# khoa_so_dien_tu.net
KiCad netlist of a schematic drawn in Altium Designer
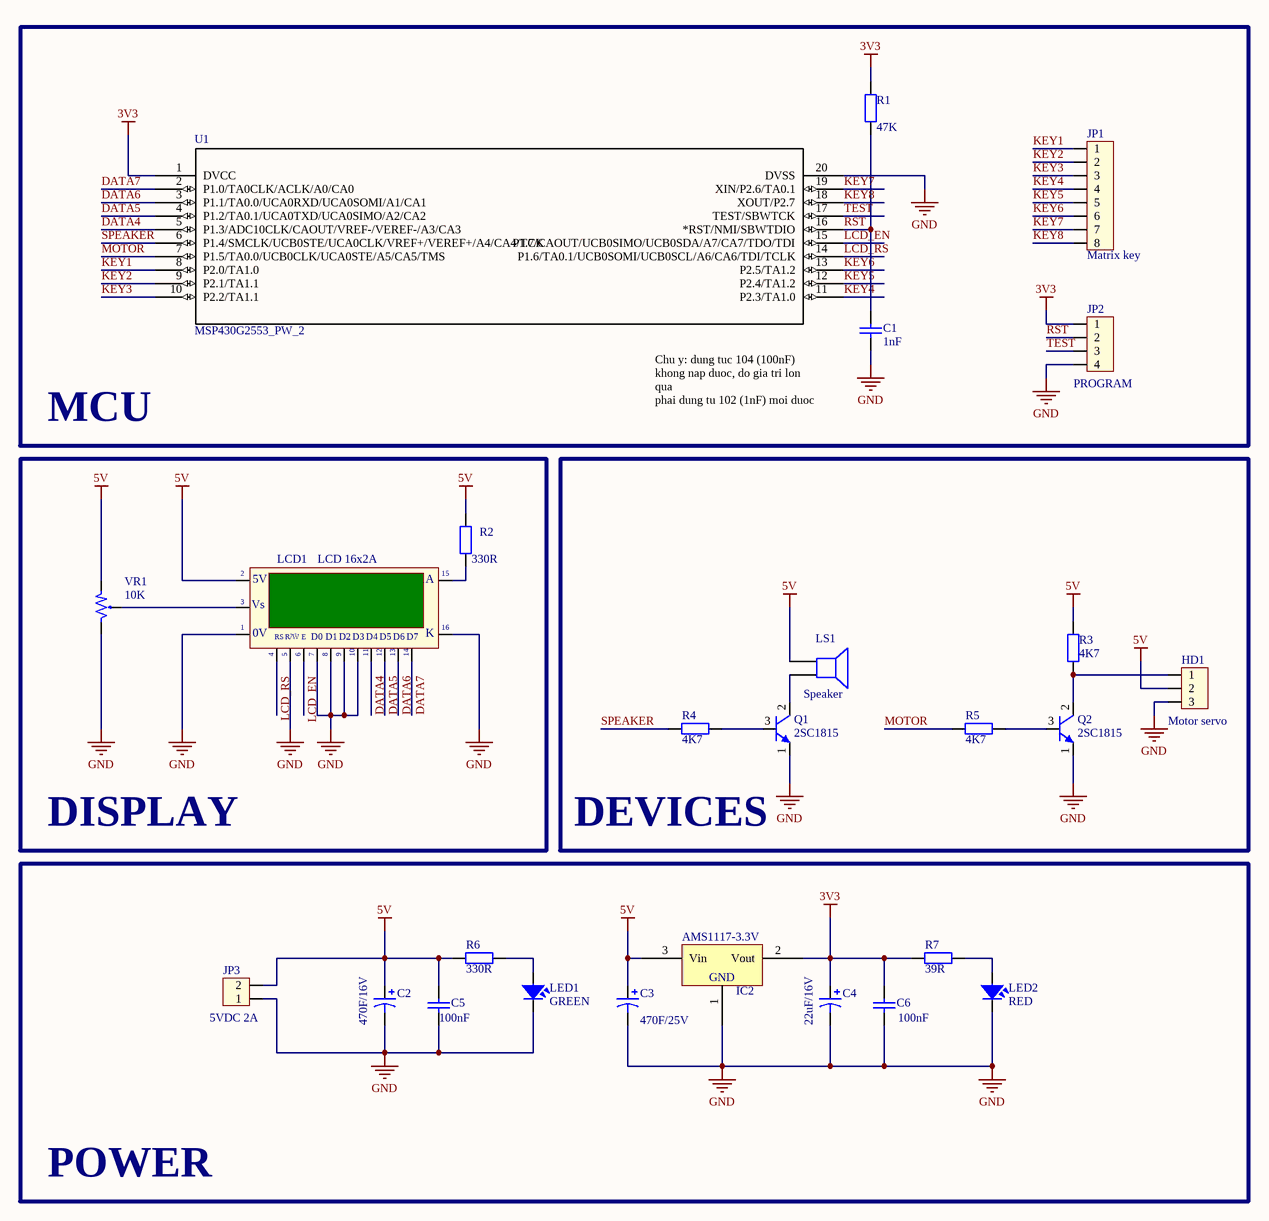
[diagram p0: khoa so dien tu.SchDoc]

(export (version "E")
  (design (tool "Eeschema 10.0.6"))
  (components
    (comp (ref "C1")
      (value "1nF")
      (footprint "Tu gom 104")
      (description "Capacitor")
      (fields (field (name "Comment") "Cap") (field (name "PUBLISHER") "Altium Limited"))
      (libsource (lib "Miscellaneous Devices") (part "Cap"))
    )
    (comp (ref "C2")
      (value "470F/16V")
      (footprint "CAP_470UF_16V")
      (description "Polarized Capacitor (Radial)")
      (fields (field (name "Comment") "Cap Pol1") (field (name "PUBLISHER") "Altium Limited"))
      (libsource (lib "Miscellaneous Devices") (part "Cap Pol1"))
    )
    (comp (ref "C3")
      (value "470F/25V")
      (footprint "CAP_470UF_25V")
      (description "Polarized Capacitor (Radial)")
      (fields (field (name "Comment") "Cap Pol1") (field (name "PUBLISHER") "Altium Limited"))
      (libsource (lib "Miscellaneous Devices") (part "Cap Pol1"))
    )
    (comp (ref "C4")
      (value "22uF/16V")
      (footprint "CAP_22UF_16V")
      (description "Polarized Capacitor (Radial)")
      (fields (field (name "Comment") "Cap Pol1") (field (name "PUBLISHER") "Altium Limited"))
      (libsource (lib "Miscellaneous Devices") (part "Cap Pol1"))
    )
    (comp (ref "C5")
      (value "100nF")
      (footprint "Tu gom 104")
      (description "Capacitor")
      (fields (field (name "Comment") "Cap") (field (name "PUBLISHER") "Altium Limited"))
      (libsource (lib "Miscellaneous Devices") (part "Cap"))
    )
    (comp (ref "C6")
      (value "100nF")
      (footprint "Tu gom 104")
      (description "Capacitor")
      (fields (field (name "Comment") "Cap") (field (name "PUBLISHER") "Altium Limited"))
      (libsource (lib "Miscellaneous Devices") (part "Cap"))
    )
    (comp (ref "HD1")
      (value "Motor servo")
      (footprint "Header_3")
      (description "Header 3 (Green)")
      (libsource (lib "lpson") (part "Hed3"))
    )
    (comp (ref "IC2")
      (value "AMS1117-3.3V")
      (footprint "AMS1117-3.3V")
      (libsource (lib "LuanVanPIR") (part "AMS1117"))
    )
    (comp (ref "JP1")
      (value "Matrix key")
      (footprint "Header_8")
      (description "Connector 8")
      (libsource (lib "lpson") (part "Con8"))
    )
    (comp (ref "JP2")
      (value "PROGRAM")
      (footprint "Header_4")
      (description "Connector 4")
      (libsource (lib "lpson") (part "Con4"))
    )
    (comp (ref "JP3")
      (value "5VDC 2A")
      (footprint "CON2")
      (description "Connector 2")
      (libsource (lib "lpson") (part "Con2"))
    )
    (comp (ref "LCD1")
      (value "LCD 16x2A")
      (footprint "LCD16x2")
      (description "LCD dipslay 16 char, 2 line")
      (libsource (lib "VNELEK") (part "LCD16x2A"))
    )
    (comp (ref "LED1")
      (value "GREEN")
      (footprint "LED3G")
      (description "LED Single colour Green and Red")
      (libsource (lib "VNELEK") (part "LED"))
    )
    (comp (ref "LED2")
      (value "RED")
      (footprint "LED3R")
      (description "LED Single colour Green and Red")
      (libsource (lib "VNELEK") (part "LED"))
    )
    (comp (ref "LS1")
      (value "Speaker")
      (footprint "SPEAKER")
      (description "Loudspeaker")
      (fields (field (name "PUBLISHER") "Altium Limited"))
      (libsource (lib "Miscellaneous Devices") (part "Speaker"))
    )
    (comp (ref "Q1")
      (value "2SC1815")
      (footprint "2SC1815")
      (description "Trans NPN 50V 150mA TO-92")
      (libsource (lib "lpson") (part "2SC1815"))
    )
    (comp (ref "Q2")
      (value "2SC1815")
      (footprint "2SC1815")
      (description "Trans NPN 50V 150mA TO-92")
      (libsource (lib "lpson") (part "2SC1815"))
    )
    (comp (ref "R1")
      (value "47K")
      (footprint "RES 1/4W CFR25")
      (description "Resistor")
      (fields (field (name "Comment") "Res2") (field (name "PUBLISHER") "Altium Limited"))
      (libsource (lib "") (part "Res2_2"))
    )
    (comp (ref "R2")
      (value "330R")
      (footprint "RES 1/4W CFR25")
      (description "Resistor")
      (fields (field (name "Comment") "Res2") (field (name "PUBLISHER") "Altium Limited"))
      (libsource (lib "") (part "Res2_2"))
    )
    (comp (ref "R3")
      (value "4K7")
      (footprint "RES 1/4W CFR25")
      (description "Resistor")
      (fields (field (name "Comment") "Res2") (field (name "PUBLISHER") "Altium Limited"))
      (libsource (lib "") (part "Res2_2"))
    )
    (comp (ref "R4")
      (value "4K7")
      (footprint "RES 1/4W CFR25")
      (description "Resistor")
      (fields (field (name "Comment") "Res2") (field (name "PUBLISHER") "Altium Limited"))
      (libsource (lib "Miscellaneous Devices") (part "Res2"))
    )
    (comp (ref "R5")
      (value "4K7")
      (footprint "RES 1/4W CFR25")
      (description "Resistor")
      (fields (field (name "Comment") "Res2") (field (name "PUBLISHER") "Altium Limited"))
      (libsource (lib "Miscellaneous Devices") (part "Res2"))
    )
    (comp (ref "R6")
      (value "330R")
      (footprint "RES 1/4W CFR25")
      (description "Resistor")
      (fields (field (name "Comment") "Res2") (field (name "PUBLISHER") "Altium Limited"))
      (libsource (lib "") (part "Res2_1"))
    )
    (comp (ref "R7")
      (value "39R")
      (footprint "RES 1/4W CFR25")
      (description "Resistor")
      (fields (field (name "Comment") "Res2") (field (name "PUBLISHER") "Altium Limited"))
      (libsource (lib "") (part "Res2_1"))
    )
    (comp (ref "U1")
      (value "MSP430G2553_PW_2")
      (footprint "MSP430G2553")
      (description "Imported")
      (fields
        (field (name "MANUFACTURER_PART_NUMBER") "msp430g2553_pw_20")
        (field (name "GENERIC_PART_NUMBER") "MSP430G2553")
      )
      (libsource (lib "MSP430G2553_PW_2") (part "MSP430G2553_PW_2"))
    )
    (comp (ref "VR1")
      (value "10K")
      (footprint "VR1")
      (description "Var Resistor")
      (libsource (lib "VNELEK") (part "VR1"))
    )
  )
  (nets
    (net (code "1") (name "/DATA4") (class "Default")
      (node (ref "LCD1") (pin "11") (pinfunction "D4_11") (pintype "passive"))
      (node (ref "U1") (pin "5") (pinfunction "P1.3/ADC10CLK/CAOUT/VREF-/VEREF-/A3/CA3_5") (pintype "bidirectional"))
    )
    (net (code "2") (name "/DATA5") (class "Default")
      (node (ref "LCD1") (pin "12") (pinfunction "D5_12") (pintype "passive"))
      (node (ref "U1") (pin "4") (pinfunction "P1.2/TA0.1/UCA0TXD/UCA0SIMO/A2/CA2_4") (pintype "bidirectional"))
    )
    (net (code "3") (name "/DATA6") (class "Default")
      (node (ref "LCD1") (pin "13") (pinfunction "D6_13") (pintype "passive"))
      (node (ref "U1") (pin "3") (pinfunction "P1.1/TA0.0/UCA0RXD/UCA0SOMI/A1/CA1_3") (pintype "bidirectional"))
    )
    (net (code "4") (name "/DATA7") (class "Default")
      (node (ref "LCD1") (pin "14") (pinfunction "D7_14") (pintype "passive"))
      (node (ref "U1") (pin "2") (pinfunction "P1.0/TA0CLK/ACLK/A0/CA0_2") (pintype "bidirectional"))
    )
    (net (code "5") (name "/KEY1") (class "Default")
      (node (ref "JP1") (pin "1") (pinfunction "1_1") (pintype "passive"))
      (node (ref "U1") (pin "8") (pinfunction "P2.0/TA1.0_8") (pintype "bidirectional"))
    )
    (net (code "6") (name "/KEY2") (class "Default")
      (node (ref "JP1") (pin "2") (pinfunction "2_2") (pintype "passive"))
      (node (ref "U1") (pin "9") (pinfunction "P2.1/TA1.1_9") (pintype "bidirectional"))
    )
    (net (code "7") (name "/KEY3") (class "Default")
      (node (ref "JP1") (pin "3") (pinfunction "3_3") (pintype "passive"))
      (node (ref "U1") (pin "10") (pinfunction "P2.2/TA1.1_10") (pintype "bidirectional"))
    )
    (net (code "8") (name "/KEY4") (class "Default")
      (node (ref "JP1") (pin "4") (pinfunction "4_4") (pintype "passive"))
      (node (ref "U1") (pin "11") (pinfunction "P2.3/TA1.0_11") (pintype "bidirectional"))
    )
    (net (code "9") (name "/KEY5") (class "Default")
      (node (ref "JP1") (pin "5") (pinfunction "5_5") (pintype "passive"))
      (node (ref "U1") (pin "12") (pinfunction "P2.4/TA1.2_12") (pintype "bidirectional"))
    )
    (net (code "10") (name "/KEY6") (class "Default")
      (node (ref "JP1") (pin "6") (pinfunction "6_6") (pintype "passive"))
      (node (ref "U1") (pin "13") (pinfunction "P2.5/TA1.2_13") (pintype "bidirectional"))
    )
    (net (code "11") (name "/KEY7") (class "Default")
      (node (ref "JP1") (pin "7") (pinfunction "7_7") (pintype "passive"))
      (node (ref "U1") (pin "19") (pinfunction "XIN/P2.6/TA0.1_19") (pintype "bidirectional"))
    )
    (net (code "12") (name "/KEY8") (class "Default")
      (node (ref "JP1") (pin "8") (pinfunction "8_8") (pintype "passive"))
      (node (ref "U1") (pin "18") (pinfunction "XOUT/P2.7_18") (pintype "bidirectional"))
    )
    (net (code "13") (name "/LCD_EN") (class "Default")
      (node (ref "LCD1") (pin "6") (pinfunction "~{EN}_6") (pintype "passive"))
      (node (ref "U1") (pin "15") (pinfunction "P1.7/CAOUT/UCB0SIMO/UCB0SDA/A7/CA7/TDO/TDI_15") (pintype "bidirectional"))
    )
    (net (code "14") (name "/LCD_RS") (class "Default")
      (node (ref "LCD1") (pin "4") (pinfunction "RS_4") (pintype "passive"))
      (node (ref "U1") (pin "14") (pinfunction "P1.6/TA0.1/UCB0SOMI/UCB0SCL/A6/CA6/TDI/TCLK_14") (pintype "bidirectional"))
    )
    (net (code "15") (name "/MOTOR") (class "Default")
      (node (ref "R5") (pin "1") (pinfunction "1_1") (pintype "passive"))
      (node (ref "U1") (pin "7") (pinfunction "P1.5/TA0.0/UCB0CLK/UCA0STE/A5/CA5/TMS_7") (pintype "bidirectional"))
    )
    (net (code "16") (name "/RST") (class "Default")
      (node (ref "C1") (pin "1") (pinfunction "1_1") (pintype "passive"))
      (node (ref "JP2") (pin "2") (pinfunction "2_2") (pintype "passive"))
      (node (ref "R1") (pin "1") (pinfunction "1_1") (pintype "passive"))
      (node (ref "U1") (pin "16") (pinfunction "*RST/NMI/SBWTDIO_16") (pintype "bidirectional"))
    )
    (net (code "17") (name "/SPEAKER") (class "Default")
      (node (ref "R4") (pin "1") (pinfunction "1_1") (pintype "passive"))
      (node (ref "U1") (pin "6") (pinfunction "P1.4/SMCLK/UCB0STE/UCA0CLK/VREF+/VEREF+/A4/CA4/TCK_6") (pintype "bidirectional"))
    )
    (net (code "18") (name "/TEST") (class "Default")
      (node (ref "JP2") (pin "3") (pinfunction "3_3") (pintype "passive"))
      (node (ref "U1") (pin "17") (pinfunction "TEST/SBWTCK_17") (pintype "bidirectional"))
    )
    (net (code "19") (name "3V3") (class "Default")
      (node (ref "C4") (pin "1") (pinfunction "1_1") (pintype "passive"))
      (node (ref "C6") (pin "2") (pinfunction "2_2") (pintype "passive"))
      (node (ref "IC2") (pin "2") (pinfunction "Vout_2") (pintype "passive"))
      (node (ref "JP2") (pin "1") (pinfunction "1_1") (pintype "passive"))
      (node (ref "R1") (pin "2") (pinfunction "2_2") (pintype "passive"))
      (node (ref "R7") (pin "2") (pinfunction "2_2") (pintype "passive"))
      (node (ref "U1") (pin "1") (pinfunction "DVCC_1") (pintype "power_in"))
    )
    (net (code "20") (name "5V") (class "Default")
      (node (ref "C2") (pin "1") (pinfunction "1_1") (pintype "passive"))
      (node (ref "C3") (pin "1") (pinfunction "1_1") (pintype "passive"))
      (node (ref "C5") (pin "2") (pinfunction "2_2") (pintype "passive"))
      (node (ref "HD1") (pin "2") (pinfunction "2_2") (pintype "passive"))
      (node (ref "IC2") (pin "3") (pinfunction "Vin_3") (pintype "passive"))
      (node (ref "JP3") (pin "2") (pinfunction "2_2") (pintype "passive"))
      (node (ref "LCD1") (pin "2") (pinfunction "VDD_2") (pintype "passive"))
      (node (ref "LS1") (pin "2") (pinfunction "2_2") (pintype "passive"))
      (node (ref "R2") (pin "2") (pinfunction "2_2") (pintype "passive"))
      (node (ref "R3") (pin "2") (pinfunction "2_2") (pintype "passive"))
      (node (ref "R6") (pin "2") (pinfunction "2_2") (pintype "passive"))
      (node (ref "VR1") (pin "1") (pinfunction "1_1") (pintype "passive"))
    )
    (net (code "21") (name "GND") (class "Default")
      (node (ref "C1") (pin "2") (pinfunction "2_2") (pintype "passive"))
      (node (ref "C2") (pin "2") (pinfunction "2_2") (pintype "passive"))
      (node (ref "C3") (pin "2") (pinfunction "2_2") (pintype "passive"))
      (node (ref "C4") (pin "2") (pinfunction "2_2") (pintype "passive"))
      (node (ref "C5") (pin "1") (pinfunction "1_1") (pintype "passive"))
      (node (ref "C6") (pin "1") (pinfunction "1_1") (pintype "passive"))
      (node (ref "HD1") (pin "3") (pinfunction "3_3") (pintype "passive"))
      (node (ref "IC2") (pin "1") (pinfunction "GND_1") (pintype "passive"))
      (node (ref "JP2") (pin "4") (pinfunction "4_4") (pintype "passive"))
      (node (ref "JP3") (pin "1") (pinfunction "1_1") (pintype "passive"))
      (node (ref "LCD1") (pin "1") (pinfunction "GND_1") (pintype "passive"))
      (node (ref "LCD1") (pin "10") (pinfunction "D3_10") (pintype "passive"))
      (node (ref "LCD1") (pin "16") (pinfunction "K_16") (pintype "passive"))
      (node (ref "LCD1") (pin "5") (pinfunction "R/~{W}_5") (pintype "passive"))
      (node (ref "LCD1") (pin "7") (pinfunction "D0_7") (pintype "passive"))
      (node (ref "LCD1") (pin "8") (pinfunction "D1_8") (pintype "passive"))
      (node (ref "LCD1") (pin "9") (pinfunction "D2_9") (pintype "passive"))
      (node (ref "LED1") (pin "2") (pinfunction "2_2") (pintype "passive"))
      (node (ref "LED2") (pin "2") (pinfunction "2_2") (pintype "passive"))
      (node (ref "Q1") (pin "1") (pinfunction "E_1") (pintype "passive"))
      (node (ref "Q2") (pin "1") (pinfunction "E_1") (pintype "passive"))
      (node (ref "U1") (pin "20") (pinfunction "DVSS_20") (pintype "power_in"))
      (node (ref "VR1") (pin "3") (pinfunction "3_3") (pintype "passive"))
    )
    (net (code "22") (name "Net-(LCD1-A)") (class "Default")
      (node (ref "LCD1") (pin "15") (pinfunction "A_15") (pintype "passive"))
      (node (ref "R2") (pin "1") (pinfunction "1_1") (pintype "passive"))
    )
    (net (code "23") (name "Net-(LCD1-VEE)") (class "Default")
      (node (ref "LCD1") (pin "3") (pinfunction "VEE_3") (pintype "passive"))
      (node (ref "VR1") (pin "2") (pinfunction "2_2") (pintype "passive"))
    )
    (net (code "24") (name "Net-(LED1-Pad1)") (class "Default")
      (node (ref "LED1") (pin "1") (pinfunction "1_1") (pintype "passive"))
      (node (ref "R6") (pin "1") (pinfunction "1_1") (pintype "passive"))
    )
    (net (code "25") (name "Net-(LED2-Pad1)") (class "Default")
      (node (ref "LED2") (pin "1") (pinfunction "1_1") (pintype "passive"))
      (node (ref "R7") (pin "1") (pinfunction "1_1") (pintype "passive"))
    )
    (net (code "26") (name "Net-(Q1-B)") (class "Default")
      (node (ref "Q1") (pin "3") (pinfunction "B_3") (pintype "passive"))
      (node (ref "R4") (pin "2") (pinfunction "2_2") (pintype "passive"))
    )
    (net (code "27") (name "Net-(Q1-C)") (class "Default")
      (node (ref "LS1") (pin "1") (pinfunction "1_1") (pintype "passive"))
      (node (ref "Q1") (pin "2") (pinfunction "C_2") (pintype "passive"))
    )
    (net (code "28") (name "Net-(Q2-B)") (class "Default")
      (node (ref "Q2") (pin "3") (pinfunction "B_3") (pintype "passive"))
      (node (ref "R5") (pin "2") (pinfunction "2_2") (pintype "passive"))
    )
    (net (code "29") (name "Net-(Q2-C)") (class "Default")
      (node (ref "HD1") (pin "1") (pinfunction "1_1") (pintype "passive"))
      (node (ref "Q2") (pin "2") (pinfunction "C_2") (pintype "passive"))
      (node (ref "R3") (pin "1") (pinfunction "1_1") (pintype "passive"))
    )
  )
)
